# Signal_Integrity_4L.net
KiCad netlist of a schematic drawn in Altium Designer
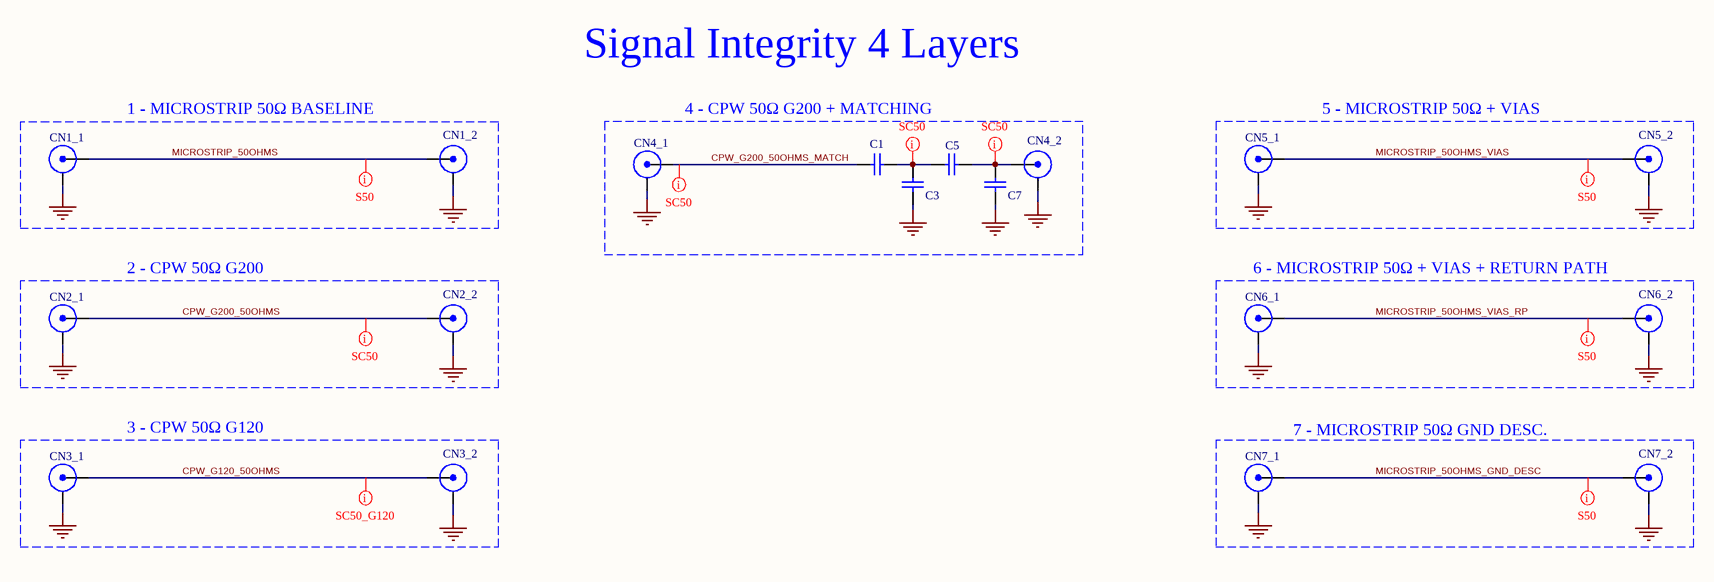
[diagram p0: Signal_Integrity_4L.SchDoc]

(export (version "E")
  (design (tool "Eeschema 10.0.6"))
  (components
    (comp (ref "C1")
      (value "CAP SMD 0402")
      (footprint "0402")
      (description "0402")
      (libsource (lib "Impedance") (part "CAP SMD 0402"))
    )
    (comp (ref "C3")
      (value "CAP SMD 0402")
      (footprint "0402")
      (description "0402")
      (libsource (lib "Impedance") (part "CAP SMD 0402"))
    )
    (comp (ref "C5")
      (value "CAP SMD 0402")
      (footprint "0402")
      (description "0402")
      (libsource (lib "Impedance") (part "CAP SMD 0402"))
    )
    (comp (ref "C7")
      (value "CAP SMD 0402")
      (footprint "0402")
      (description "0402")
      (libsource (lib "Impedance") (part "CAP SMD 0402"))
    )
    (comp (ref "CN1_1")
      (value "SMA-KE EDGE")
      (footprint "SMA-KE EDGE")
      (description "SMA Connector Receptacle, Female Socket 50Ohm Board Edge, End Launch Solder")
      (fields
        (field (name "MOUSER PART NUMBER") "712-CONSMA020.062-G")
        (field (name "MANUFACTURER_PART_NUMBER") "CONSMA020.062-G")
      )
      (libsource (lib "Impedance") (part "SMA-KE EDGE"))
    )
    (comp (ref "CN1_2")
      (value "SMA-KE EDGE")
      (footprint "SMA-KE EDGE")
      (description "SMA Connector Receptacle, Female Socket 50Ohm Board Edge, End Launch Solder")
      (fields
        (field (name "MOUSER PART NUMBER") "712-CONSMA020.062-G")
        (field (name "MANUFACTURER_PART_NUMBER") "CONSMA020.062-G")
      )
      (libsource (lib "Impedance") (part "SMA-KE EDGE"))
    )
    (comp (ref "CN2_1")
      (value "SMA-KE EDGE")
      (footprint "SMA-KE EDGE")
      (description "SMA Connector Receptacle, Female Socket 50Ohm Board Edge, End Launch Solder")
      (fields
        (field (name "MOUSER PART NUMBER") "712-CONSMA020.062-G")
        (field (name "MANUFACTURER_PART_NUMBER") "CONSMA020.062-G")
      )
      (libsource (lib "Impedance") (part "SMA-KE EDGE"))
    )
    (comp (ref "CN2_2")
      (value "SMA-KE EDGE")
      (footprint "SMA-KE EDGE")
      (description "SMA Connector Receptacle, Female Socket 50Ohm Board Edge, End Launch Solder")
      (fields
        (field (name "MOUSER PART NUMBER") "712-CONSMA020.062-G")
        (field (name "MANUFACTURER_PART_NUMBER") "CONSMA020.062-G")
      )
      (libsource (lib "Impedance") (part "SMA-KE EDGE"))
    )
    (comp (ref "CN3_1")
      (value "SMA-KE EDGE")
      (footprint "SMA-KE EDGE")
      (description "SMA Connector Receptacle, Female Socket 50Ohm Board Edge, End Launch Solder")
      (fields
        (field (name "MOUSER PART NUMBER") "712-CONSMA020.062-G")
        (field (name "MANUFACTURER_PART_NUMBER") "CONSMA020.062-G")
      )
      (libsource (lib "Impedance") (part "SMA-KE EDGE"))
    )
    (comp (ref "CN3_2")
      (value "SMA-KE EDGE")
      (footprint "SMA-KE EDGE")
      (description "SMA Connector Receptacle, Female Socket 50Ohm Board Edge, End Launch Solder")
      (fields
        (field (name "MOUSER PART NUMBER") "712-CONSMA020.062-G")
        (field (name "MANUFACTURER_PART_NUMBER") "CONSMA020.062-G")
      )
      (libsource (lib "Impedance") (part "SMA-KE EDGE"))
    )
    (comp (ref "CN4_1")
      (value "SMA-KE EDGE")
      (footprint "SMA-KE EDGE")
      (description "SMA Connector Receptacle, Female Socket 50Ohm Board Edge, End Launch Solder")
      (fields
        (field (name "MOUSER PART NUMBER") "712-CONSMA020.062-G")
        (field (name "MANUFACTURER_PART_NUMBER") "CONSMA020.062-G")
      )
      (libsource (lib "Impedance") (part "SMA-KE EDGE"))
    )
    (comp (ref "CN4_2")
      (value "SMA-KE EDGE")
      (footprint "SMA-KE EDGE")
      (description "SMA Connector Receptacle, Female Socket 50Ohm Board Edge, End Launch Solder")
      (fields
        (field (name "MOUSER PART NUMBER") "712-CONSMA020.062-G")
        (field (name "MANUFACTURER_PART_NUMBER") "CONSMA020.062-G")
      )
      (libsource (lib "Impedance") (part "SMA-KE EDGE"))
    )
    (comp (ref "CN5_1")
      (value "SMA-KE EDGE")
      (footprint "SMA-KE EDGE")
      (description "SMA Connector Receptacle, Female Socket 50Ohm Board Edge, End Launch Solder")
      (fields
        (field (name "MOUSER PART NUMBER") "712-CONSMA020.062-G")
        (field (name "MANUFACTURER_PART_NUMBER") "CONSMA020.062-G")
      )
      (libsource (lib "Impedance") (part "SMA-KE EDGE"))
    )
    (comp (ref "CN5_2")
      (value "SMA-KE EDGE")
      (footprint "SMA-KE EDGE")
      (description "SMA Connector Receptacle, Female Socket 50Ohm Board Edge, End Launch Solder")
      (fields
        (field (name "MOUSER PART NUMBER") "712-CONSMA020.062-G")
        (field (name "MANUFACTURER_PART_NUMBER") "CONSMA020.062-G")
      )
      (libsource (lib "Impedance") (part "SMA-KE EDGE"))
    )
    (comp (ref "CN6_1")
      (value "SMA-KE EDGE")
      (footprint "SMA-KE EDGE")
      (description "SMA Connector Receptacle, Female Socket 50Ohm Board Edge, End Launch Solder")
      (fields
        (field (name "MOUSER PART NUMBER") "712-CONSMA020.062-G")
        (field (name "MANUFACTURER_PART_NUMBER") "CONSMA020.062-G")
      )
      (libsource (lib "Impedance") (part "SMA-KE EDGE"))
    )
    (comp (ref "CN6_2")
      (value "SMA-KE EDGE")
      (footprint "SMA-KE EDGE")
      (description "SMA Connector Receptacle, Female Socket 50Ohm Board Edge, End Launch Solder")
      (fields
        (field (name "MOUSER PART NUMBER") "712-CONSMA020.062-G")
        (field (name "MANUFACTURER_PART_NUMBER") "CONSMA020.062-G")
      )
      (libsource (lib "Impedance") (part "SMA-KE EDGE"))
    )
    (comp (ref "CN7_1")
      (value "SMA-KE EDGE")
      (footprint "SMA-KE EDGE")
      (description "SMA Connector Receptacle, Female Socket 50Ohm Board Edge, End Launch Solder")
      (fields
        (field (name "MOUSER PART NUMBER") "712-CONSMA020.062-G")
        (field (name "MANUFACTURER_PART_NUMBER") "CONSMA020.062-G")
      )
      (libsource (lib "Impedance") (part "SMA-KE EDGE"))
    )
    (comp (ref "CN7_2")
      (value "SMA-KE EDGE")
      (footprint "SMA-KE EDGE")
      (description "SMA Connector Receptacle, Female Socket 50Ohm Board Edge, End Launch Solder")
      (fields
        (field (name "MOUSER PART NUMBER") "712-CONSMA020.062-G")
        (field (name "MANUFACTURER_PART_NUMBER") "CONSMA020.062-G")
      )
      (libsource (lib "Impedance") (part "SMA-KE EDGE"))
    )
  )
  (nets
    (net (code "1") (name "/CPW_G120_50OHMS") (class "Default")
      (node (ref "CN3_1") (pin "1") (pinfunction "SIGNAL_1") (pintype "passive"))
      (node (ref "CN3_2") (pin "1") (pinfunction "SIGNAL_1") (pintype "passive"))
    )
    (net (code "2") (name "/CPW_G200_50OHMS") (class "Default")
      (node (ref "CN2_1") (pin "1") (pinfunction "SIGNAL_1") (pintype "passive"))
      (node (ref "CN2_2") (pin "1") (pinfunction "SIGNAL_1") (pintype "passive"))
    )
    (net (code "3") (name "/CPW_G200_50OHMS_MATCH") (class "Default")
      (node (ref "C1") (pin "1") (pinfunction "1_1") (pintype "passive"))
      (node (ref "CN4_1") (pin "1") (pinfunction "SIGNAL_1") (pintype "passive"))
    )
    (net (code "4") (name "/MICROSTRIP_50OHMS") (class "Default")
      (node (ref "CN1_1") (pin "1") (pinfunction "SIGNAL_1") (pintype "passive"))
      (node (ref "CN1_2") (pin "1") (pinfunction "SIGNAL_1") (pintype "passive"))
    )
    (net (code "5") (name "/MICROSTRIP_50OHMS_GND_DESC") (class "Default")
      (node (ref "CN7_1") (pin "1") (pinfunction "SIGNAL_1") (pintype "passive"))
      (node (ref "CN7_2") (pin "1") (pinfunction "SIGNAL_1") (pintype "passive"))
    )
    (net (code "6") (name "/MICROSTRIP_50OHMS_VIAS") (class "Default")
      (node (ref "CN5_1") (pin "1") (pinfunction "SIGNAL_1") (pintype "passive"))
      (node (ref "CN5_2") (pin "1") (pinfunction "SIGNAL_1") (pintype "passive"))
    )
    (net (code "7") (name "/MICROSTRIP_50OHMS_VIAS_RP") (class "Default")
      (node (ref "CN6_1") (pin "1") (pinfunction "SIGNAL_1") (pintype "passive"))
      (node (ref "CN6_2") (pin "1") (pinfunction "SIGNAL_1") (pintype "passive"))
    )
    (net (code "8") (name "GND1") (class "Default")
      (node (ref "CN1_1") (pin "2") (pinfunction "GND_2") (pintype "passive"))
      (node (ref "CN1_2") (pin "2") (pinfunction "GND_2") (pintype "passive"))
    )
    (net (code "9") (name "GND2") (class "Default")
      (node (ref "CN2_1") (pin "2") (pinfunction "GND_2") (pintype "passive"))
      (node (ref "CN2_2") (pin "2") (pinfunction "GND_2") (pintype "passive"))
    )
    (net (code "10") (name "GND3") (class "Default")
      (node (ref "CN3_1") (pin "2") (pinfunction "GND_2") (pintype "passive"))
      (node (ref "CN3_2") (pin "2") (pinfunction "GND_2") (pintype "passive"))
    )
    (net (code "11") (name "GND4") (class "Default")
      (node (ref "C3") (pin "1") (pinfunction "1_1") (pintype "passive"))
      (node (ref "C7") (pin "1") (pinfunction "1_1") (pintype "passive"))
      (node (ref "CN4_1") (pin "2") (pinfunction "GND_2") (pintype "passive"))
      (node (ref "CN4_2") (pin "2") (pinfunction "GND_2") (pintype "passive"))
    )
    (net (code "12") (name "GND5") (class "Default")
      (node (ref "CN5_1") (pin "2") (pinfunction "GND_2") (pintype "passive"))
      (node (ref "CN5_2") (pin "2") (pinfunction "GND_2") (pintype "passive"))
    )
    (net (code "13") (name "GND6") (class "Default")
      (node (ref "CN6_1") (pin "2") (pinfunction "GND_2") (pintype "passive"))
      (node (ref "CN6_2") (pin "2") (pinfunction "GND_2") (pintype "passive"))
    )
    (net (code "14") (name "GND7") (class "Default")
      (node (ref "CN7_1") (pin "2") (pinfunction "GND_2") (pintype "passive"))
      (node (ref "CN7_2") (pin "2") (pinfunction "GND_2") (pintype "passive"))
    )
    (net (code "15") (name "Net-(C1-Pad2)") (class "Default")
      (node (ref "C1") (pin "2") (pinfunction "2_2") (pintype "passive"))
      (node (ref "C3") (pin "2") (pinfunction "2_2") (pintype "passive"))
      (node (ref "C5") (pin "1") (pinfunction "1_1") (pintype "passive"))
    )
    (net (code "16") (name "Net-(CN4_2-SIGNAL)") (class "Default")
      (node (ref "C5") (pin "2") (pinfunction "2_2") (pintype "passive"))
      (node (ref "C7") (pin "2") (pinfunction "2_2") (pintype "passive"))
      (node (ref "CN4_2") (pin "1") (pinfunction "SIGNAL_1") (pintype "passive"))
    )
  )
)
